# jk_flip-flop.net
KiCad netlist of a schematic drawn in EAGLE
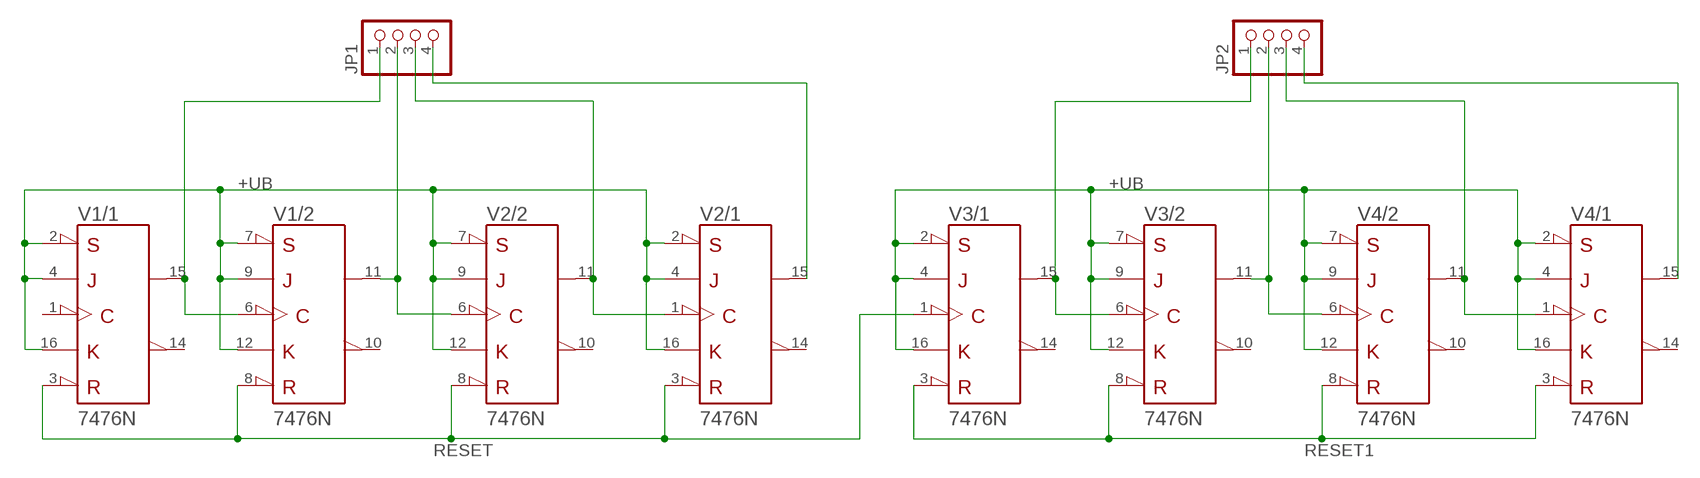
[diagram p0: schematic, sheet 1]

(export (version "E")
  (design (tool "Eeschema 10.0.6"))
  (components
    (comp (ref "JP1")
      (value "PINHD-1X4")
      (footprint "eagle-import:1X04")
      (libsource (lib "eagle-import") (part "PINHD-1X4"))
    )
    (comp (ref "JP2")
      (value "PINHD-1X4")
      (footprint "eagle-import:1X04")
      (libsource (lib "eagle-import") (part "PINHD-1X4"))
    )
    (comp (ref "V1")
      (value "7476N")
      (footprint "eagle-import:DIL16")
      (libsource (lib "eagle-import") (part "7476N"))
    )
    (comp (ref "V2")
      (value "7476N")
      (footprint "eagle-import:DIL16")
      (libsource (lib "eagle-import") (part "7476N"))
    )
    (comp (ref "V3")
      (value "7476N")
      (footprint "eagle-import:DIL16")
      (libsource (lib "eagle-import") (part "7476N"))
    )
    (comp (ref "V4")
      (value "7476N")
      (footprint "eagle-import:DIL16")
      (libsource (lib "eagle-import") (part "7476N"))
    )
  )
  (nets
    (net (code "1") (name "/+UB") (class "Default")
      (node (ref "V1") (pin "12") (pinfunction "K_12") (pintype "input"))
      (node (ref "V1") (pin "16") (pinfunction "K_16") (pintype "input"))
      (node (ref "V1") (pin "2") (pinfunction "~{PRE}_2") (pintype "input"))
      (node (ref "V1") (pin "4") (pinfunction "J_4") (pintype "input"))
      (node (ref "V1") (pin "7") (pinfunction "~{PRE}_7") (pintype "input"))
      (node (ref "V1") (pin "9") (pinfunction "J_9") (pintype "input"))
      (node (ref "V2") (pin "12") (pinfunction "K_12") (pintype "input"))
      (node (ref "V2") (pin "16") (pinfunction "K_16") (pintype "input"))
      (node (ref "V2") (pin "2") (pinfunction "~{PRE}_2") (pintype "input"))
      (node (ref "V2") (pin "4") (pinfunction "J_4") (pintype "input"))
      (node (ref "V2") (pin "7") (pinfunction "~{PRE}_7") (pintype "input"))
      (node (ref "V2") (pin "9") (pinfunction "J_9") (pintype "input"))
      (node (ref "V3") (pin "12") (pinfunction "K_12") (pintype "input"))
      (node (ref "V3") (pin "16") (pinfunction "K_16") (pintype "input"))
      (node (ref "V3") (pin "2") (pinfunction "~{PRE}_2") (pintype "input"))
      (node (ref "V3") (pin "4") (pinfunction "J_4") (pintype "input"))
      (node (ref "V3") (pin "7") (pinfunction "~{PRE}_7") (pintype "input"))
      (node (ref "V3") (pin "9") (pinfunction "J_9") (pintype "input"))
      (node (ref "V4") (pin "12") (pinfunction "K_12") (pintype "input"))
      (node (ref "V4") (pin "16") (pinfunction "K_16") (pintype "input"))
      (node (ref "V4") (pin "2") (pinfunction "~{PRE}_2") (pintype "input"))
      (node (ref "V4") (pin "4") (pinfunction "J_4") (pintype "input"))
      (node (ref "V4") (pin "7") (pinfunction "~{PRE}_7") (pintype "input"))
      (node (ref "V4") (pin "9") (pinfunction "J_9") (pintype "input"))
    )
    (net (code "2") (name "/RESET") (class "Default")
      (node (ref "V1") (pin "3") (pinfunction "~{CLR}_3") (pintype "input"))
      (node (ref "V1") (pin "8") (pinfunction "~{CLR}_8") (pintype "input"))
      (node (ref "V2") (pin "3") (pinfunction "~{CLR}_3") (pintype "input"))
      (node (ref "V2") (pin "8") (pinfunction "~{CLR}_8") (pintype "input"))
      (node (ref "V3") (pin "1") (pinfunction "CLK_1") (pintype "input"))
    )
    (net (code "3") (name "/RESET1") (class "Default")
      (node (ref "V3") (pin "3") (pinfunction "~{CLR}_3") (pintype "input"))
      (node (ref "V3") (pin "8") (pinfunction "~{CLR}_8") (pintype "input"))
      (node (ref "V4") (pin "3") (pinfunction "~{CLR}_3") (pintype "input"))
      (node (ref "V4") (pin "8") (pinfunction "~{CLR}_8") (pintype "input"))
    )
    (net (code "4") (name "Net-(V1C-Q)") (class "Default")
      (node (ref "JP1") (pin "1") (pinfunction "1_1") (pintype "passive"))
      (node (ref "V1") (pin "15") (pinfunction "Q_15") (pintype "output"))
      (node (ref "V1") (pin "6") (pinfunction "CLK_6") (pintype "input"))
    )
    (net (code "5") (name "Net-(V1D-Q)") (class "Default")
      (node (ref "JP1") (pin "2") (pinfunction "2_2") (pintype "passive"))
      (node (ref "V1") (pin "11") (pinfunction "Q_11") (pintype "output"))
      (node (ref "V2") (pin "6") (pinfunction "CLK_6") (pintype "input"))
    )
    (net (code "6") (name "Net-(V2C-CLK)") (class "Default")
      (node (ref "JP1") (pin "3") (pinfunction "3_3") (pintype "passive"))
      (node (ref "V2") (pin "1") (pinfunction "CLK_1") (pintype "input"))
      (node (ref "V2") (pin "11") (pinfunction "Q_11") (pintype "output"))
    )
    (net (code "7") (name "Net-(V2C-Q)") (class "Default")
      (node (ref "JP1") (pin "4") (pinfunction "4_4") (pintype "passive"))
      (node (ref "V2") (pin "15") (pinfunction "Q_15") (pintype "output"))
    )
    (net (code "8") (name "Net-(V3C-Q)") (class "Default")
      (node (ref "JP2") (pin "1") (pinfunction "1_1") (pintype "passive"))
      (node (ref "V3") (pin "15") (pinfunction "Q_15") (pintype "output"))
      (node (ref "V3") (pin "6") (pinfunction "CLK_6") (pintype "input"))
    )
    (net (code "9") (name "Net-(V3D-Q)") (class "Default")
      (node (ref "JP2") (pin "2") (pinfunction "2_2") (pintype "passive"))
      (node (ref "V3") (pin "11") (pinfunction "Q_11") (pintype "output"))
      (node (ref "V4") (pin "6") (pinfunction "CLK_6") (pintype "input"))
    )
    (net (code "10") (name "Net-(V4C-CLK)") (class "Default")
      (node (ref "JP2") (pin "3") (pinfunction "3_3") (pintype "passive"))
      (node (ref "V4") (pin "1") (pinfunction "CLK_1") (pintype "input"))
      (node (ref "V4") (pin "11") (pinfunction "Q_11") (pintype "output"))
    )
    (net (code "11") (name "Net-(V4C-Q)") (class "Default")
      (node (ref "JP2") (pin "4") (pinfunction "4_4") (pintype "passive"))
      (node (ref "V4") (pin "15") (pinfunction "Q_15") (pintype "output"))
    )
    (net (code "12") (name "unconnected-(V1C-CLK-Pad1)") (class "Default")
      (node (ref "V1") (pin "1") (pinfunction "CLK_1") (pintype "input"))
    )
    (net (code "13") (name "unconnected-(V1C-~{Q}-Pad14)") (class "Default")
      (node (ref "V1") (pin "14") (pinfunction "~{Q}_14") (pintype "output"))
    )
    (net (code "14") (name "unconnected-(V1D-~{Q}-Pad10)") (class "Default")
      (node (ref "V1") (pin "10") (pinfunction "~{Q}_10") (pintype "output"))
    )
    (net (code "15") (name "unconnected-(V2C-~{Q}-Pad14)") (class "Default")
      (node (ref "V2") (pin "14") (pinfunction "~{Q}_14") (pintype "output"))
    )
    (net (code "16") (name "unconnected-(V2D-~{Q}-Pad10)") (class "Default")
      (node (ref "V2") (pin "10") (pinfunction "~{Q}_10") (pintype "output"))
    )
    (net (code "17") (name "unconnected-(V3C-~{Q}-Pad14)") (class "Default")
      (node (ref "V3") (pin "14") (pinfunction "~{Q}_14") (pintype "output"))
    )
    (net (code "18") (name "unconnected-(V3D-~{Q}-Pad10)") (class "Default")
      (node (ref "V3") (pin "10") (pinfunction "~{Q}_10") (pintype "output"))
    )
    (net (code "19") (name "unconnected-(V4C-~{Q}-Pad14)") (class "Default")
      (node (ref "V4") (pin "14") (pinfunction "~{Q}_14") (pintype "output"))
    )
    (net (code "20") (name "unconnected-(V4D-~{Q}-Pad10)") (class "Default")
      (node (ref "V4") (pin "10") (pinfunction "~{Q}_10") (pintype "output"))
    )
  )
)
